# logic.net
KiCad netlist of a schematic drawn in EAGLE
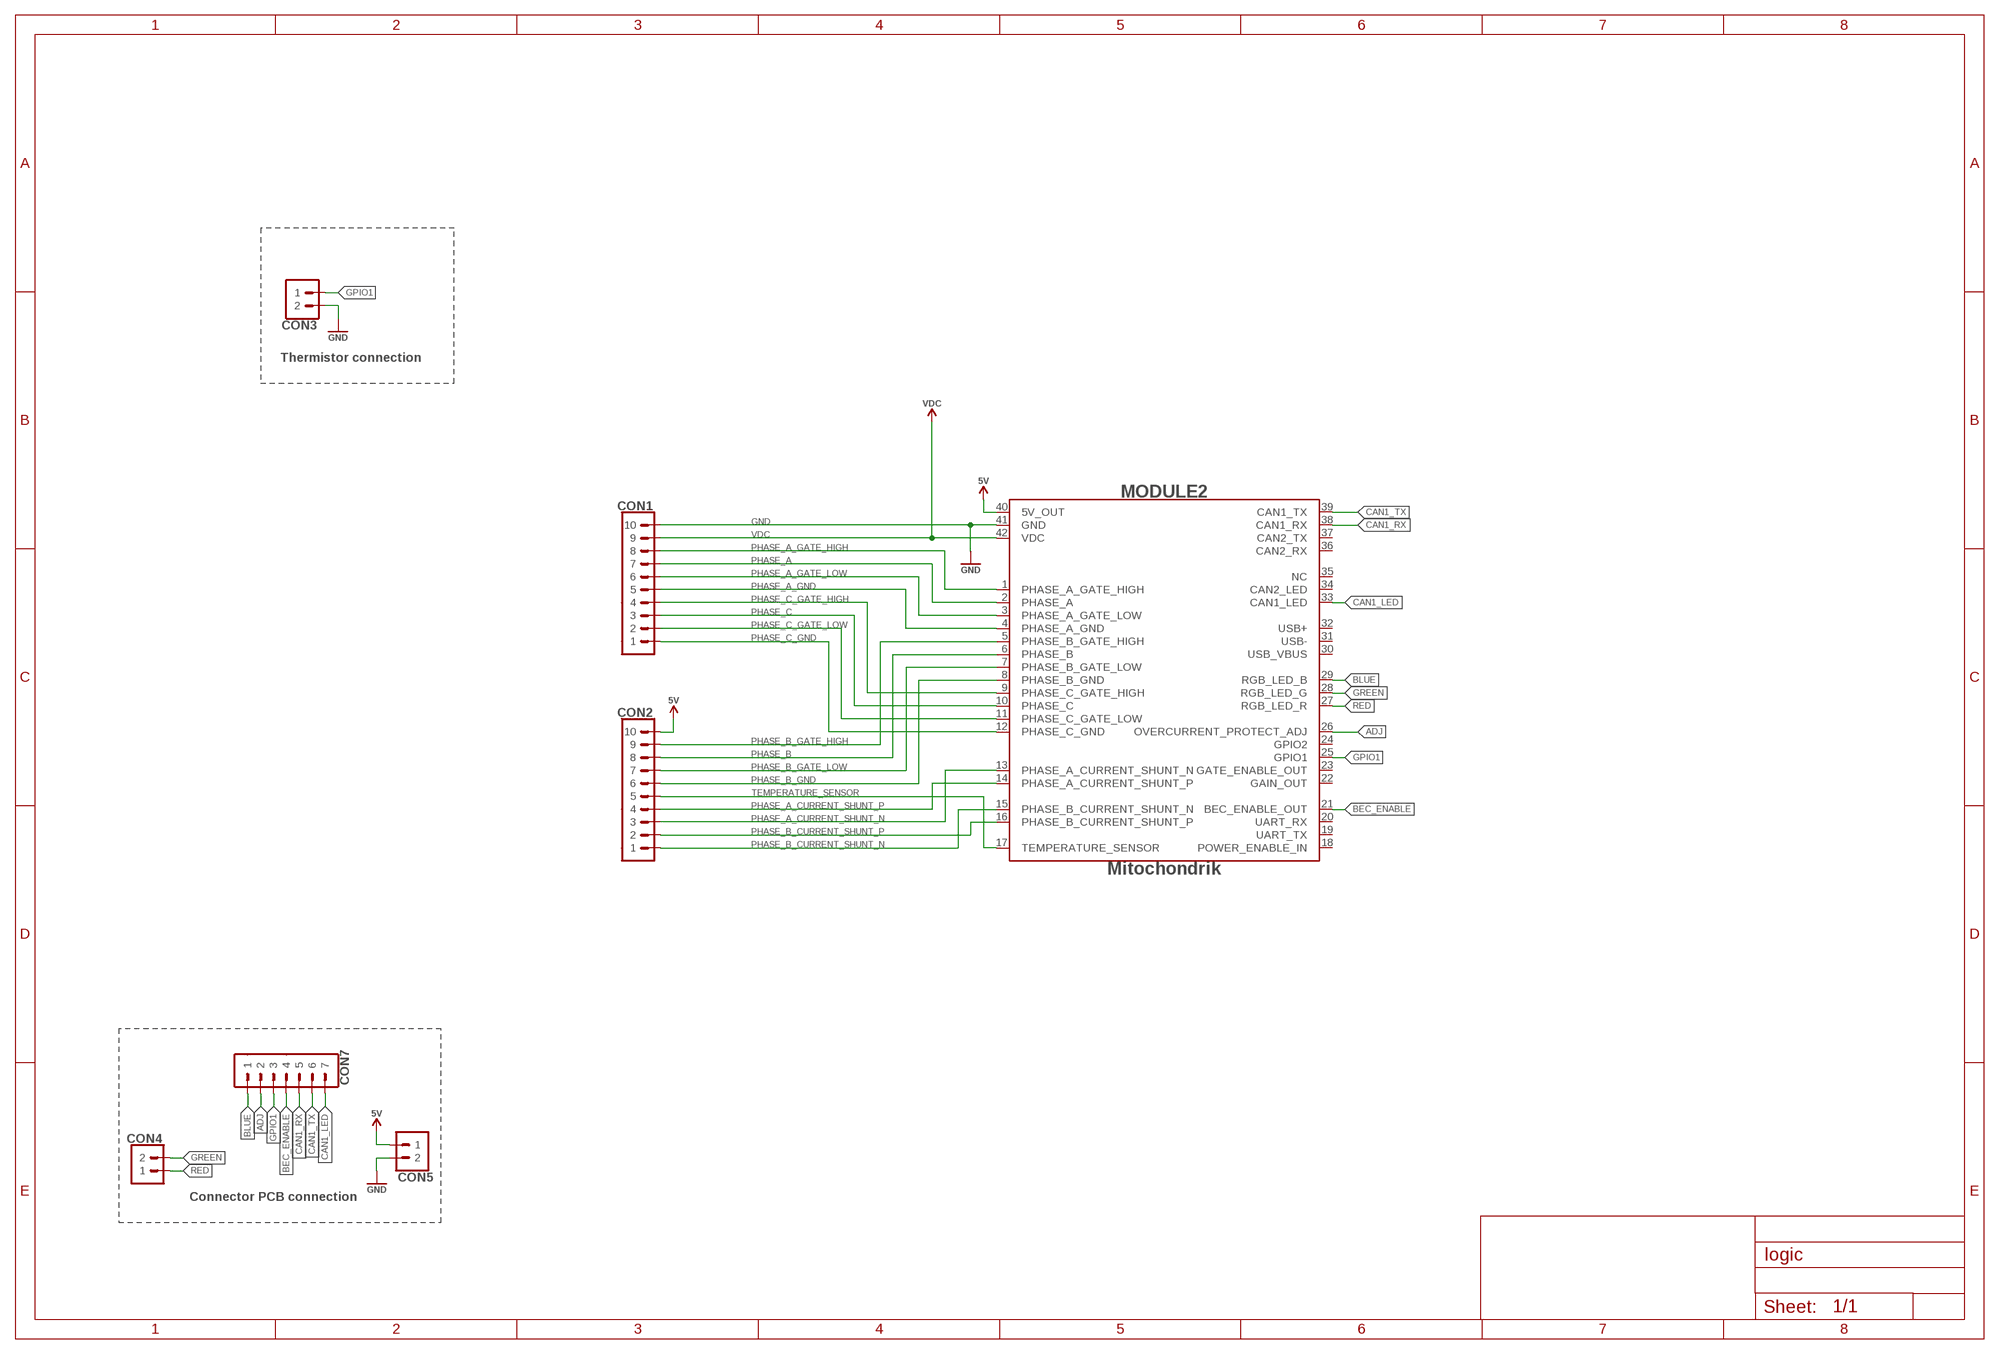
[diagram p0: schematic, sheet 1]

(export (version "E")
  (design (tool "Eeschema 10.0.6"))
  (components
    (comp (ref "CON1")
      (value "PINHEAD_1X10-2")
      (footprint "eagle-import:1X10-PTH_2")
      (libsource (lib "eagle-import") (part "PINHEAD_1X10-2"))
    )
    (comp (ref "CON2")
      (value "PINHEAD_1X10-2")
      (footprint "eagle-import:1X10-PTH_2")
      (libsource (lib "eagle-import") (part "PINHEAD_1X10-2"))
    )
    (comp (ref "CON3")
      (value "PINHEAD_1X02-2")
      (footprint "eagle-import:1X02-PTH-2")
      (libsource (lib "eagle-import") (part "PINHEAD_1X02-2"))
    )
    (comp (ref "CON4")
      (value "PINHEAD_1X02-2")
      (footprint "eagle-import:1X02-PTH-2")
      (libsource (lib "eagle-import") (part "PINHEAD_1X02-2"))
    )
    (comp (ref "CON5")
      (value "PINHEAD_1X02-2")
      (footprint "eagle-import:1X02-PTH-2")
      (libsource (lib "eagle-import") (part "PINHEAD_1X02-2"))
    )
    (comp (ref "CON7")
      (value "PINHEAD_1X07-2")
      (footprint "eagle-import:1X07-PTH-2")
      (libsource (lib "eagle-import") (part "PINHEAD_1X07-2"))
    )
    (comp (ref "MODULE2")
      (value "MITOHONDRIQUE_V0.2-TH")
      (footprint "eagle-import:MITOHONDRIQUE-TH")
      (fields (field (name "MANF#") "Mitochondrik") (field (name "MANF") "Zubax Robotics"))
      (libsource (lib "eagle-import") (part "MITOHONDRIQUE_V0.2-TH"))
    )
  )
  (nets
    (net (code "1") (name "/PHASE_A") (class "Default")
      (node (ref "CON1") (pin "7") (pinfunction "7_7") (pintype "passive"))
      (node (ref "MODULE2") (pin "2") (pinfunction "PHASE_A_2") (pintype "input"))
    )
    (net (code "2") (name "/PHASE_A_CURRENT_SHUNT_N") (class "Default")
      (node (ref "CON2") (pin "3") (pinfunction "3_3") (pintype "passive"))
      (node (ref "MODULE2") (pin "13") (pinfunction "PHASE_A_CURRENT_SHUNT_N_13") (pintype "input"))
    )
    (net (code "3") (name "/PHASE_A_CURRENT_SHUNT_P") (class "Default")
      (node (ref "CON2") (pin "4") (pinfunction "4_4") (pintype "passive"))
      (node (ref "MODULE2") (pin "14") (pinfunction "PHASE_A_CURRENT_SHUNT_P_14") (pintype "input"))
    )
    (net (code "4") (name "/PHASE_A_GATE_HIGH") (class "Default")
      (node (ref "CON1") (pin "8") (pinfunction "8_8") (pintype "passive"))
      (node (ref "MODULE2") (pin "1") (pinfunction "PHASE_A_GATE_HIGH_1") (pintype "output"))
    )
    (net (code "5") (name "/PHASE_A_GATE_LOW") (class "Default")
      (node (ref "CON1") (pin "6") (pinfunction "6_6") (pintype "passive"))
      (node (ref "MODULE2") (pin "3") (pinfunction "PHASE_A_GATE_LOW_3") (pintype "output"))
    )
    (net (code "6") (name "/PHASE_A_GND") (class "Default")
      (node (ref "CON1") (pin "5") (pinfunction "5_5") (pintype "passive"))
      (node (ref "MODULE2") (pin "4") (pinfunction "PHASE_A_GND_4") (pintype "input"))
    )
    (net (code "7") (name "/PHASE_B") (class "Default")
      (node (ref "CON2") (pin "8") (pinfunction "8_8") (pintype "passive"))
      (node (ref "MODULE2") (pin "6") (pinfunction "PHASE_B_6") (pintype "input"))
    )
    (net (code "8") (name "/PHASE_B_CURRENT_SHUNT_N") (class "Default")
      (node (ref "CON2") (pin "1") (pinfunction "1_1") (pintype "passive"))
      (node (ref "MODULE2") (pin "15") (pinfunction "PHASE_B_CURRENT_SHUNT_N_15") (pintype "input"))
    )
    (net (code "9") (name "/PHASE_B_CURRENT_SHUNT_P") (class "Default")
      (node (ref "CON2") (pin "2") (pinfunction "2_2") (pintype "passive"))
      (node (ref "MODULE2") (pin "16") (pinfunction "PHASE_B_CURRENT_SHUNT_P_16") (pintype "input"))
    )
    (net (code "10") (name "/PHASE_B_GATE_HIGH") (class "Default")
      (node (ref "CON2") (pin "9") (pinfunction "9_9") (pintype "passive"))
      (node (ref "MODULE2") (pin "5") (pinfunction "PHASE_B_GATE_HIGH_5") (pintype "output"))
    )
    (net (code "11") (name "/PHASE_B_GATE_LOW") (class "Default")
      (node (ref "CON2") (pin "7") (pinfunction "7_7") (pintype "passive"))
      (node (ref "MODULE2") (pin "7") (pinfunction "PHASE_B_GATE_LOW_7") (pintype "output"))
    )
    (net (code "12") (name "/PHASE_B_GND") (class "Default")
      (node (ref "CON2") (pin "6") (pinfunction "6_6") (pintype "passive"))
      (node (ref "MODULE2") (pin "8") (pinfunction "PHASE_B_GND_8") (pintype "input"))
    )
    (net (code "13") (name "/PHASE_C") (class "Default")
      (node (ref "CON1") (pin "3") (pinfunction "3_3") (pintype "passive"))
      (node (ref "MODULE2") (pin "10") (pinfunction "PHASE_C_10") (pintype "input"))
    )
    (net (code "14") (name "/PHASE_C_GATE_HIGH") (class "Default")
      (node (ref "CON1") (pin "4") (pinfunction "4_4") (pintype "passive"))
      (node (ref "MODULE2") (pin "9") (pinfunction "PHASE_C_GATE_HIGH_9") (pintype "output"))
    )
    (net (code "15") (name "/PHASE_C_GATE_LOW") (class "Default")
      (node (ref "CON1") (pin "2") (pinfunction "2_2") (pintype "passive"))
      (node (ref "MODULE2") (pin "11") (pinfunction "PHASE_C_GATE_LOW_11") (pintype "output"))
    )
    (net (code "16") (name "/PHASE_C_GND") (class "Default")
      (node (ref "CON1") (pin "1") (pinfunction "1_1") (pintype "passive"))
      (node (ref "MODULE2") (pin "12") (pinfunction "PHASE_C_GND_12") (pintype "input"))
    )
    (net (code "17") (name "/TEMPERATURE_SENSOR") (class "Default")
      (node (ref "CON2") (pin "5") (pinfunction "5_5") (pintype "passive"))
      (node (ref "MODULE2") (pin "17") (pinfunction "TEMPERATURE_SENSOR_17") (pintype "input"))
    )
    (net (code "18") (name "5V") (class "Default")
      (node (ref "CON2") (pin "10") (pinfunction "10_10") (pintype "passive"))
      (node (ref "CON5") (pin "1") (pinfunction "1_1") (pintype "passive"))
      (node (ref "MODULE2") (pin "40") (pinfunction "5V_OUT_40") (pintype "power_in"))
    )
    (net (code "19") (name "ADJ") (class "Default")
      (node (ref "CON7") (pin "2") (pinfunction "2_2") (pintype "passive"))
      (node (ref "MODULE2") (pin "26") (pinfunction "OVERCURRENT_PROTECT_ADJ_26") (pintype "input"))
    )
    (net (code "20") (name "BEC_ENABLE") (class "Default")
      (node (ref "CON7") (pin "4") (pinfunction "4_4") (pintype "passive"))
      (node (ref "MODULE2") (pin "21") (pinfunction "BEC_ENABLE_OUT_21") (pintype "output"))
    )
    (net (code "21") (name "BLUE") (class "Default")
      (node (ref "CON7") (pin "1") (pinfunction "1_1") (pintype "passive"))
      (node (ref "MODULE2") (pin "29") (pinfunction "RGB_LED_B_29") (pintype "output"))
    )
    (net (code "22") (name "CAN1_LED") (class "Default")
      (node (ref "CON7") (pin "7") (pinfunction "7_7") (pintype "passive"))
      (node (ref "MODULE2") (pin "33") (pinfunction "CAN1_LED_33") (pintype "output"))
    )
    (net (code "23") (name "CAN1_RX") (class "Default")
      (node (ref "CON7") (pin "5") (pinfunction "5_5") (pintype "passive"))
      (node (ref "MODULE2") (pin "38") (pinfunction "CAN1_RX_38") (pintype "input"))
    )
    (net (code "24") (name "CAN1_TX") (class "Default")
      (node (ref "CON7") (pin "6") (pinfunction "6_6") (pintype "passive"))
      (node (ref "MODULE2") (pin "39") (pinfunction "CAN1_TX_39") (pintype "output"))
    )
    (net (code "25") (name "GND") (class "Default")
      (node (ref "CON1") (pin "10") (pinfunction "10_10") (pintype "passive"))
      (node (ref "CON3") (pin "2") (pinfunction "2_2") (pintype "passive"))
      (node (ref "CON5") (pin "2") (pinfunction "2_2") (pintype "passive"))
      (node (ref "MODULE2") (pin "41") (pinfunction "GND_41") (pintype "power_in"))
    )
    (net (code "26") (name "GPIO1") (class "Default")
      (node (ref "CON3") (pin "1") (pinfunction "1_1") (pintype "passive"))
      (node (ref "CON7") (pin "3") (pinfunction "3_3") (pintype "passive"))
      (node (ref "MODULE2") (pin "25") (pinfunction "GPIO1_25") (pintype "bidirectional"))
    )
    (net (code "27") (name "GREEN") (class "Default")
      (node (ref "CON4") (pin "2") (pinfunction "2_2") (pintype "passive"))
      (node (ref "MODULE2") (pin "28") (pinfunction "RGB_LED_G_28") (pintype "output"))
    )
    (net (code "28") (name "RED") (class "Default")
      (node (ref "CON4") (pin "1") (pinfunction "1_1") (pintype "passive"))
      (node (ref "MODULE2") (pin "27") (pinfunction "RGB_LED_R_27") (pintype "output"))
    )
    (net (code "29") (name "VDC") (class "Default")
      (node (ref "CON1") (pin "9") (pinfunction "9_9") (pintype "passive"))
      (node (ref "MODULE2") (pin "42") (pinfunction "VDC_42") (pintype "power_in"))
    )
    (net (code "30") (name "unconnected-(MODULE2-CAN2_LED-Pad34)") (class "Default")
      (node (ref "MODULE2") (pin "34") (pinfunction "CAN2_LED_34") (pintype "output"))
    )
    (net (code "31") (name "unconnected-(MODULE2-CAN2_RX-Pad36)") (class "Default")
      (node (ref "MODULE2") (pin "36") (pinfunction "CAN2_RX_36") (pintype "input"))
    )
    (net (code "32") (name "unconnected-(MODULE2-CAN2_TX-Pad37)") (class "Default")
      (node (ref "MODULE2") (pin "37") (pinfunction "CAN2_TX_37") (pintype "output"))
    )
    (net (code "33") (name "unconnected-(MODULE2-GAIN_OUT-Pad22)") (class "Default")
      (node (ref "MODULE2") (pin "22") (pinfunction "GAIN_OUT_22") (pintype "output"))
    )
    (net (code "34") (name "unconnected-(MODULE2-GATE_ENABLE_OUT-Pad23)") (class "Default")
      (node (ref "MODULE2") (pin "23") (pinfunction "GATE_ENABLE_OUT_23") (pintype "output"))
    )
    (net (code "35") (name "unconnected-(MODULE2-GPIO2-Pad24)") (class "Default")
      (node (ref "MODULE2") (pin "24") (pinfunction "GPIO2_24") (pintype "bidirectional"))
    )
    (net (code "36") (name "unconnected-(MODULE2-NC-Pad35)") (class "Default")
      (node (ref "MODULE2") (pin "35") (pinfunction "NC_35") (pintype "no_connect"))
    )
    (net (code "37") (name "unconnected-(MODULE2-POWER_ENABLE_IN-Pad18)") (class "Default")
      (node (ref "MODULE2") (pin "18") (pinfunction "POWER_ENABLE_IN_18") (pintype "input"))
    )
    (net (code "38") (name "unconnected-(MODULE2-UART_RX-Pad20)") (class "Default")
      (node (ref "MODULE2") (pin "20") (pinfunction "UART_RX_20") (pintype "input"))
    )
    (net (code "39") (name "unconnected-(MODULE2-UART_TX-Pad19)") (class "Default")
      (node (ref "MODULE2") (pin "19") (pinfunction "UART_TX_19") (pintype "output"))
    )
    (net (code "40") (name "unconnected-(MODULE2-USB+-Pad32)") (class "Default")
      (node (ref "MODULE2") (pin "32") (pinfunction "USB+_32") (pintype "bidirectional"))
    )
    (net (code "41") (name "unconnected-(MODULE2-USB--Pad31)") (class "Default")
      (node (ref "MODULE2") (pin "31") (pinfunction "USB-_31") (pintype "bidirectional"))
    )
    (net (code "42") (name "unconnected-(MODULE2-USB_VBUS-Pad30)") (class "Default")
      (node (ref "MODULE2") (pin "30") (pinfunction "USB_VBUS_30") (pintype "input"))
    )
  )
)
